# 3_lowpass_old_library.net
KiCad netlist of a schematic drawn in EAGLE
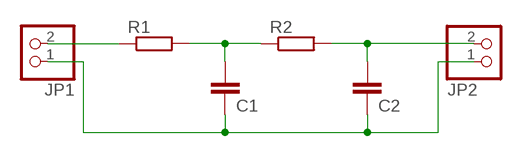
[diagram p0: schematic, sheet 1]

(export (version "E")
  (design (tool "Eeschema 10.0.6"))
  (components
    (comp (ref "C1")
      (value "C-EUC1206")
      (footprint "eagle-import:C1206")
      (libsource (lib "eagle-import") (part "C-EUC1206"))
    )
    (comp (ref "C2")
      (value "C-EUC1206")
      (footprint "eagle-import:C1206")
      (libsource (lib "eagle-import") (part "C-EUC1206"))
    )
    (comp (ref "JP1")
      (value "PINHD-1X2")
      (footprint "eagle-import:1X02")
      (libsource (lib "eagle-import") (part "PINHD-1X2"))
    )
    (comp (ref "JP2")
      (value "PINHD-1X2")
      (footprint "eagle-import:1X02")
      (libsource (lib "eagle-import") (part "PINHD-1X2"))
    )
    (comp (ref "R1")
      (value "R-EU_M1206")
      (footprint "eagle-import:M1206")
      (libsource (lib "eagle-import") (part "R-EU_M1206"))
    )
    (comp (ref "R2")
      (value "R-EU_M1206")
      (footprint "eagle-import:M1206")
      (libsource (lib "eagle-import") (part "R-EU_M1206"))
    )
  )
  (nets
    (net (code "1") (name "Net-(C1-Pad1)") (class "Default")
      (node (ref "C1") (pin "1") (pinfunction "1_1") (pintype "passive"))
      (node (ref "C2") (pin "1") (pinfunction "1_1") (pintype "passive"))
      (node (ref "JP1") (pin "1") (pinfunction "1_1") (pintype "passive"))
      (node (ref "JP2") (pin "1") (pinfunction "1_1") (pintype "passive"))
    )
    (net (code "2") (name "Net-(C1-Pad2)") (class "Default")
      (node (ref "C1") (pin "2") (pinfunction "2_2") (pintype "passive"))
      (node (ref "R1") (pin "2") (pinfunction "2_2") (pintype "passive"))
      (node (ref "R2") (pin "1") (pinfunction "1_1") (pintype "passive"))
    )
    (net (code "3") (name "Net-(C2-Pad2)") (class "Default")
      (node (ref "C2") (pin "2") (pinfunction "2_2") (pintype "passive"))
      (node (ref "JP2") (pin "2") (pinfunction "2_2") (pintype "passive"))
      (node (ref "R2") (pin "2") (pinfunction "2_2") (pintype "passive"))
    )
    (net (code "4") (name "Net-(JP1-Pad2)") (class "Default")
      (node (ref "JP1") (pin "2") (pinfunction "2_2") (pintype "passive"))
      (node (ref "R1") (pin "1") (pinfunction "1_1") (pintype "passive"))
    )
  )
)
